# Sheet1.net
KiCad netlist of a schematic drawn in Altium Designer
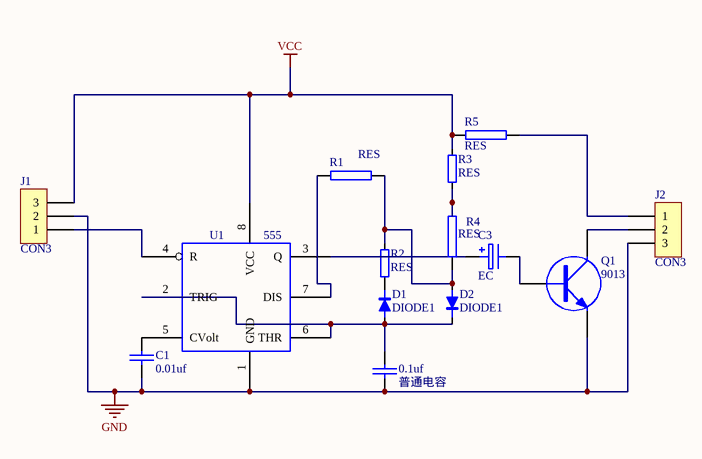
[diagram p0: Sheet1.SchDoc]

(export (version "E")
  (design (tool "Eeschema 10.0.6"))
  (components
    (comp (ref "0.1uf")
      (value "普通电容")
      (footprint "RAD0.2")
      (description "Capacitor")
      (libsource (lib "电容") (part "普通电容"))
    )
    (comp (ref "C1")
      (value "0.01uf")
      (footprint "RAD0.2")
      (description "Capacitor")
      (libsource (lib "电容") (part "普通电容"))
    )
    (comp (ref "C3") (value "EC") (footprint "RB.1/.2") (libsource (lib "电容") (part "EC")))
    (comp (ref "D1") (value "DIODE1") (footprint "DIODE0.4A") (libsource (lib "常用元件库") (part "DIODE1")))
    (comp (ref "D2") (value "DIODE1") (footprint "DIODE0.4A") (libsource (lib "常用元件库") (part "DIODE1")))
    (comp (ref "J1") (value "CON3") (footprint "SIP3") (libsource (lib "") (part "CON3_1")))
    (comp (ref "J2") (value "CON3") (footprint "SIP3") (libsource (lib "常用元件库") (part "CON3")))
    (comp (ref "Q1") (value "9013") (footprint "901#") (libsource (lib "SCH封装库") (part "NPN9013")))
    (comp (ref "R1") (value "RES") (footprint "AXIAL0.5") (libsource (lib "常用元件库") (part "RES")))
    (comp (ref "R2") (value "RES") (footprint "AXIAL0.5") (libsource (lib "电阻") (part "RES")))
    (comp (ref "R3") (value "RES") (footprint "AXIAL0.5") (libsource (lib "电阻") (part "RES")))
    (comp (ref "R4") (value "RES") (footprint "AXIAL0.5") (libsource (lib "常用元件库") (part "RES")))
    (comp (ref "R5") (value "RES") (footprint "AXIAL0.5") (libsource (lib "常用元件库") (part "RES")))
    (comp (ref "U1") (value "555") (footprint "DIP-8") (libsource (lib "数字集成电路1") (part "555")))
  )
  (nets
    (net (code "1") (name "GND") (class "Default")
      (node (ref "0.1uf") (pin "2") (pinfunction "2_2") (pintype "passive"))
      (node (ref "C1") (pin "2") (pinfunction "2_2") (pintype "passive"))
      (node (ref "J1") (pin "2") (pinfunction "2_2") (pintype "passive"))
      (node (ref "J2") (pin "3") (pinfunction "3_3") (pintype "passive"))
      (node (ref "Q1") (pin "1") (pinfunction "E_1") (pintype "passive"))
      (node (ref "U1") (pin "1") (pinfunction "GND_1") (pintype "passive"))
    )
    (net (code "2") (name "Net-(C3-E)") (class "Default")
      (node (ref "C3") (pin "2") (pinfunction "E_2") (pintype "passive"))
      (node (ref "Q1") (pin "2") (pinfunction "B_2") (pintype "passive"))
    )
    (net (code "3") (name "Net-(D1-PadK)") (class "Default")
      (node (ref "D1") (pin "K") (pinfunction "K_K") (pintype "passive"))
      (node (ref "R2") (pin "1") (pinfunction "1_1") (pintype "passive"))
    )
    (net (code "4") (name "Net-(D2-PadA)") (class "Default")
      (node (ref "D2") (pin "A") (pinfunction "A_A") (pintype "passive"))
      (node (ref "R1") (pin "2") (pinfunction "2_2") (pintype "passive"))
      (node (ref "R2") (pin "2") (pinfunction "2_2") (pintype "passive"))
      (node (ref "R4") (pin "1") (pinfunction "1_1") (pintype "passive"))
    )
    (net (code "5") (name "Net-(J2-Pad1)") (class "Default")
      (node (ref "J2") (pin "1") (pinfunction "1_1") (pintype "passive"))
      (node (ref "R5") (pin "2") (pinfunction "2_2") (pintype "passive"))
    )
    (net (code "6") (name "Net-(Q1-C)") (class "Default")
      (node (ref "J2") (pin "2") (pinfunction "2_2") (pintype "passive"))
      (node (ref "Q1") (pin "3") (pinfunction "C_3") (pintype "passive"))
    )
    (net (code "7") (name "Net-(R3-Pad1)") (class "Default")
      (node (ref "R3") (pin "1") (pinfunction "1_1") (pintype "passive"))
      (node (ref "R4") (pin "2") (pinfunction "2_2") (pintype "passive"))
    )
    (net (code "8") (name "Net-(U1-CVolt)") (class "Default")
      (node (ref "C1") (pin "1") (pinfunction "1_1") (pintype "passive"))
      (node (ref "U1") (pin "5") (pinfunction "CVolt_5") (pintype "passive"))
    )
    (net (code "9") (name "Net-(U1-DIS)") (class "Default")
      (node (ref "R1") (pin "1") (pinfunction "1_1") (pintype "passive"))
      (node (ref "U1") (pin "7") (pinfunction "DIS_7") (pintype "passive"))
    )
    (net (code "10") (name "Net-(U1-Q)") (class "Default")
      (node (ref "C3") (pin "1") (pinfunction "1_1") (pintype "passive"))
      (node (ref "U1") (pin "3") (pinfunction "Q_3") (pintype "passive"))
    )
    (net (code "11") (name "Net-(U1-R)") (class "Default")
      (node (ref "J1") (pin "1") (pinfunction "1_1") (pintype "passive"))
      (node (ref "U1") (pin "4") (pinfunction "R_4") (pintype "passive"))
    )
    (net (code "12") (name "Net-(U1-THR)") (class "Default")
      (node (ref "0.1uf") (pin "1") (pinfunction "1_1") (pintype "passive"))
      (node (ref "D1") (pin "A") (pinfunction "A_A") (pintype "passive"))
      (node (ref "D2") (pin "K") (pinfunction "K_K") (pintype "passive"))
      (node (ref "U1") (pin "2") (pinfunction "TRIG_2") (pintype "passive"))
      (node (ref "U1") (pin "6") (pinfunction "THR_6") (pintype "passive"))
    )
    (net (code "13") (name "VCC") (class "Default")
      (node (ref "J1") (pin "3") (pinfunction "3_3") (pintype "passive"))
      (node (ref "R3") (pin "2") (pinfunction "2_2") (pintype "passive"))
      (node (ref "R5") (pin "1") (pinfunction "1_1") (pintype "passive"))
      (node (ref "U1") (pin "8") (pinfunction "VCC_8") (pintype "passive"))
    )
  )
)
